# DE-060418.net
KiCad netlist of a schematic drawn in Altium Designer
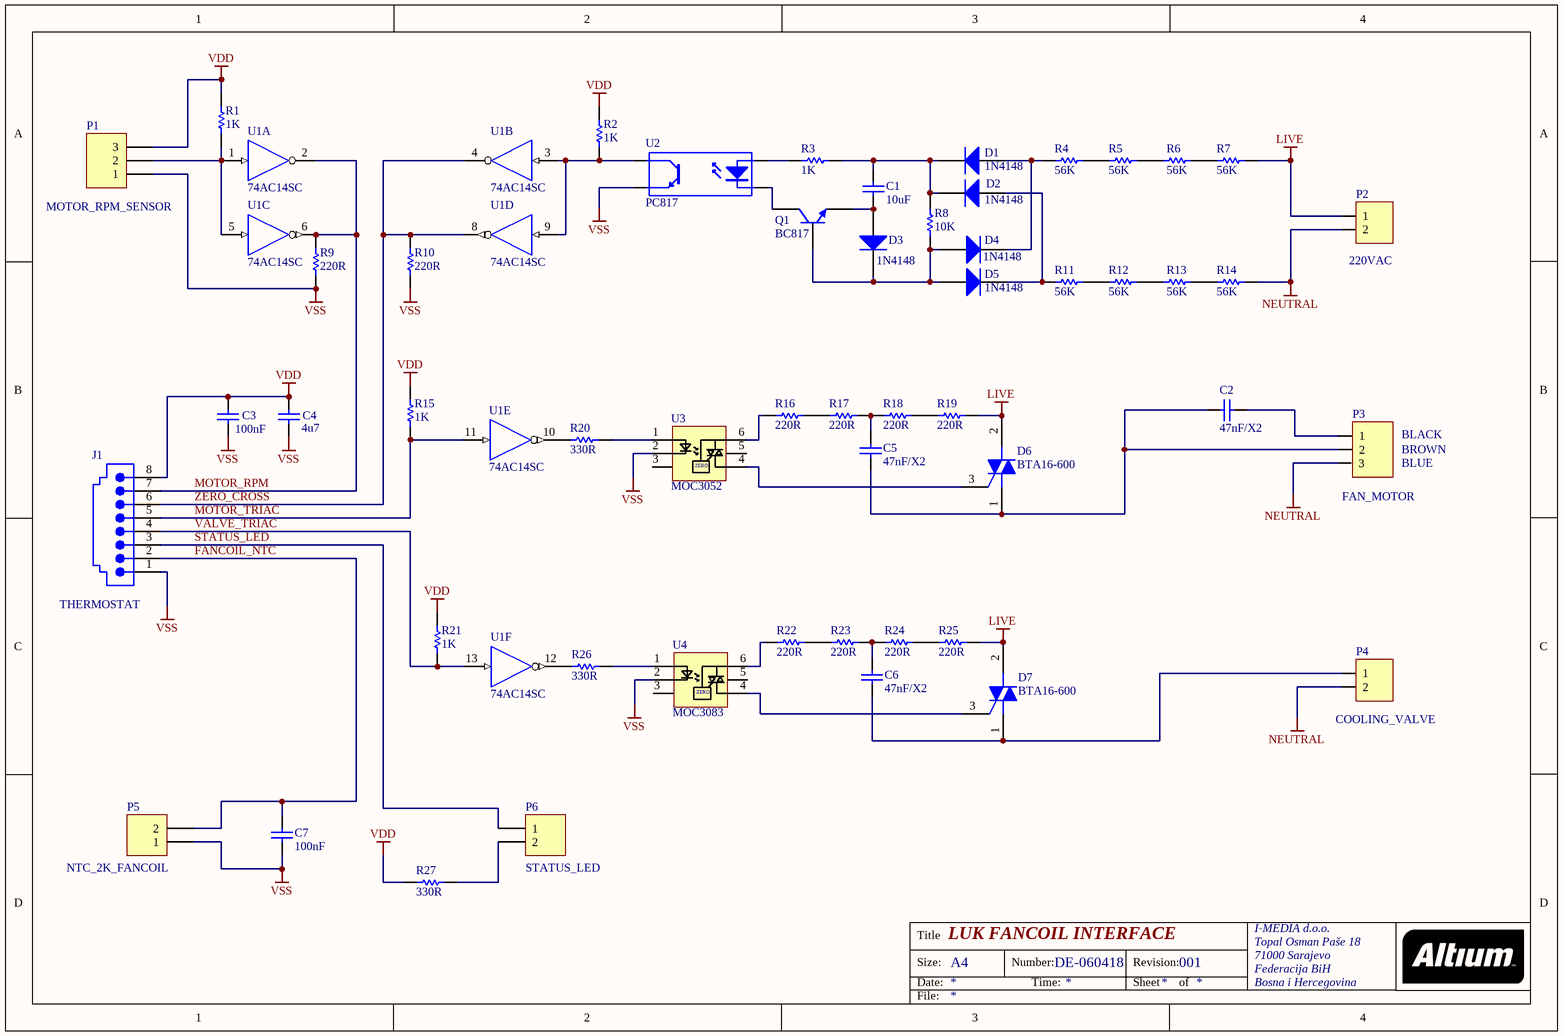
[diagram p0: DE-060418.SchDoc]

(export (version "E")
  (design (tool "Eeschema 10.0.6"))
  (components
    (comp (ref "C1")
      (value "10uF")
      (footprint "0805")
      (description "Ceramic Chip Capacitor - Standard")
      (fields (field (name "Comment") "4u7") (field (name "PUBLISHER") "Altium Limited"))
      (libsource (lib "DE-060418") (part "C0805"))
    )
    (comp (ref "C2")
      (value "47nF/X2")
      (footprint "VP52-2.5")
      (description "Dipped Radial Multilayer Ceramic Capacitor COG (NPO): 10nF")
      (fields (field (name "PUBLISHER") "Altium Limited"))
      (libsource (lib "Vishay Vitramon Ceramic Dipped Capacitor") (part "VP52BA103"))
    )
    (comp (ref "C3")
      (value "100nF")
      (footprint "0603")
      (description "Ceramic Chip Capacitor - Standard")
      (fields (field (name "PUBLISHER") "Altium Limited"))
      (libsource (lib "DE-060418") (part "C0603"))
    )
    (comp (ref "C4")
      (value "4u7")
      (footprint "0805")
      (description "Ceramic Chip Capacitor - Standard")
      (fields (field (name "PUBLISHER") "Altium Limited"))
      (libsource (lib "DE-060418") (part "C0805"))
    )
    (comp (ref "C5")
      (value "47nF/X2")
      (footprint "VP52-2.5")
      (description "Dipped Radial Multilayer Ceramic Capacitor COG (NPO): 10nF")
      (fields (field (name "PUBLISHER") "Altium Limited"))
      (libsource (lib "Vishay Vitramon Ceramic Dipped Capacitor") (part "VP52BA103"))
    )
    (comp (ref "C6")
      (value "47nF/X2")
      (footprint "VP52-2.5")
      (description "Dipped Radial Multilayer Ceramic Capacitor COG (NPO): 10nF")
      (fields (field (name "PUBLISHER") "Altium Limited"))
      (libsource (lib "Vishay Vitramon Ceramic Dipped Capacitor") (part "VP52BA103"))
    )
    (comp (ref "C7")
      (value "100nF")
      (footprint "0603")
      (description "Ceramic Chip Capacitor - Standard")
      (fields (field (name "PUBLISHER") "Altium Limited"))
      (libsource (lib "DE-060418") (part "C0603"))
    )
    (comp (ref "D1")
      (value "1N4148")
      (footprint "SOD323")
      (description "General-purpose Diode")
      (fields (field (name "PUBLISHER") "Altium Limited"))
      (libsource (lib "DE-060418") (part "BAS321"))
    )
    (comp (ref "D2")
      (value "1N4148")
      (footprint "SOD323")
      (description "General-purpose Diode")
      (fields (field (name "PUBLISHER") "Altium Limited"))
      (libsource (lib "DE-060418") (part "BAS321"))
    )
    (comp (ref "D3")
      (value "1N4148")
      (footprint "SOD323")
      (description "General-purpose Diode")
      (fields (field (name "PUBLISHER") "Altium Limited"))
      (libsource (lib "DE-060418") (part "BAS321"))
    )
    (comp (ref "D4")
      (value "1N4148")
      (footprint "SOD323")
      (description "General-purpose Diode")
      (fields (field (name "PUBLISHER") "Altium Limited"))
      (libsource (lib "DE-060418") (part "BAS321"))
    )
    (comp (ref "D5")
      (value "1N4148")
      (footprint "SOD323")
      (description "General-purpose Diode")
      (fields (field (name "PUBLISHER") "Altium Limited"))
      (libsource (lib "DE-060418") (part "BAS321"))
    )
    (comp (ref "D6")
      (value "BTA16-600")
      (footprint "ONSC-TO-220-3-221A-07")
      (description "Triacs, Silicon Bidirectional Thyristor, 3-Pin TO-220, Pb-Free, Tube")
      (fields (field (name "MANUFACTURER") "On Semiconductor") (field (name "PARTNUMBER") "BTA08-600BW3G"))
      (libsource (lib "ON Semi Triacs") (part "BTA08-600BW3G"))
    )
    (comp (ref "D7")
      (value "BTA16-600")
      (footprint "ONSC-TO-220-3-221A-07")
      (description "Triacs, Silicon Bidirectional Thyristor, 3-Pin TO-220, Pb-Free, Tube")
      (fields (field (name "MANUFACTURER") "On Semiconductor") (field (name "PARTNUMBER") "BTA08-600BW3G"))
      (libsource (lib "ON Semi Triacs") (part "BTA08-600BW3G"))
    )
    (comp (ref "J1")
      (value "THERMOSTAT")
      (footprint "15-43-8501")
      (description "Right Angle, Standard Profile, RJ-45 Keyed, Unshielded PCB Jack")
      (fields (field (name "PUBLISHER") "Altium Limited"))
      (libsource (lib "Molex Modular Jack Right Angle") (part "15-43-8501"))
    )
    (comp (ref "P1")
      (value "MOTOR_RPM_SENSOR")
      (footprint "HDR1X3")
      (description "Header, 3-Pin")
      (fields (field (name "PUBLISHER") "Altium Limited"))
      (libsource (lib "DE-060418") (part "Header 3"))
    )
    (comp (ref "P2")
      (value "220VAC")
      (footprint "TERMINAL BLOK 2")
      (description "Terminal blok konektor 3,5 mm")
      (libsource (lib "DE-060418") (part "TERMINAL BLOK 2"))
    )
    (comp (ref "P3")
      (value "FAN_MOTOR")
      (footprint "TERMINAL BLOK 3")
      (description "3 pinski terminal blok konektor")
      (libsource (lib "DE-060418") (part "TERMINAL BLOK 3"))
    )
    (comp (ref "P4")
      (value "COOLING_VALVE")
      (footprint "TERMINAL BLOK 2")
      (description "Terminal blok konektor 3,5 mm")
      (libsource (lib "DE-060418") (part "TERMINAL BLOK 2"))
    )
    (comp (ref "P5")
      (value "NTC_2K_FANCOIL")
      (footprint "HDR1X2")
      (description "Header, 2-Pin")
      (fields (field (name "PUBLISHER") "Altium Limited"))
      (libsource (lib "Miscellaneous Connectors") (part "Header 2"))
    )
    (comp (ref "P6")
      (value "STATUS_LED")
      (footprint "HDR1X2")
      (description "Header, 2-Pin")
      (fields (field (name "PUBLISHER") "Altium Limited"))
      (libsource (lib "") (part "Header 2_1"))
    )
    (comp (ref "Q1")
      (value "BC817")
      (footprint "SOT23_N")
      (description "NPN General-purpose Transistor")
      (fields (field (name "PUBLISHER") "Altium Limited"))
      (libsource (lib "DE-060418") (part "BC817"))
    )
    (comp (ref "R1")
      (value "1K")
      (footprint "6-0805")
      (fields (field (name "PUBLISHER") "Altium Limited"))
      (libsource (lib "Panasonic Resistor") (part "ERJ6BQ"))
    )
    (comp (ref "R2")
      (value "1K")
      (footprint "6-0805")
      (fields (field (name "PUBLISHER") "Altium Limited"))
      (libsource (lib "Panasonic Resistor") (part "ERJ6BQ"))
    )
    (comp (ref "R3")
      (value "1K")
      (footprint "6-0805")
      (fields (field (name "PUBLISHER") "Altium Limited"))
      (libsource (lib "Panasonic Resistor") (part "ERJ6BQ"))
    )
    (comp (ref "R4")
      (value "56K")
      (footprint "6-0805")
      (fields (field (name "PUBLISHER") "Altium Limited"))
      (libsource (lib "Panasonic Resistor") (part "ERJ6BQ"))
    )
    (comp (ref "R5")
      (value "56K")
      (footprint "6-0805")
      (fields (field (name "PUBLISHER") "Altium Limited"))
      (libsource (lib "Panasonic Resistor") (part "ERJ6BQ"))
    )
    (comp (ref "R6")
      (value "56K")
      (footprint "6-0805")
      (fields (field (name "PUBLISHER") "Altium Limited"))
      (libsource (lib "Panasonic Resistor") (part "ERJ6BQ"))
    )
    (comp (ref "R7")
      (value "56K")
      (footprint "6-0805")
      (fields (field (name "PUBLISHER") "Altium Limited"))
      (libsource (lib "Panasonic Resistor") (part "ERJ6BQ"))
    )
    (comp (ref "R8")
      (value "10K")
      (footprint "6-0805")
      (fields (field (name "PUBLISHER") "Altium Limited"))
      (libsource (lib "Panasonic Resistor") (part "ERJ6BQ"))
    )
    (comp (ref "R9")
      (value "220R")
      (footprint "6-0805")
      (fields (field (name "PUBLISHER") "Altium Limited"))
      (libsource (lib "Panasonic Resistor") (part "ERJ6BQ"))
    )
    (comp (ref "R10")
      (value "220R")
      (footprint "6-0805")
      (fields (field (name "PUBLISHER") "Altium Limited"))
      (libsource (lib "Panasonic Resistor") (part "ERJ6BQ"))
    )
    (comp (ref "R11")
      (value "56K")
      (footprint "6-0805")
      (fields (field (name "PUBLISHER") "Altium Limited"))
      (libsource (lib "Panasonic Resistor") (part "ERJ6BQ"))
    )
    (comp (ref "R12")
      (value "56K")
      (footprint "6-0805")
      (fields (field (name "PUBLISHER") "Altium Limited"))
      (libsource (lib "Panasonic Resistor") (part "ERJ6BQ"))
    )
    (comp (ref "R13")
      (value "56K")
      (footprint "6-0805")
      (fields (field (name "PUBLISHER") "Altium Limited"))
      (libsource (lib "Panasonic Resistor") (part "ERJ6BQ"))
    )
    (comp (ref "R14")
      (value "56K")
      (footprint "6-0805")
      (fields (field (name "PUBLISHER") "Altium Limited"))
      (libsource (lib "Panasonic Resistor") (part "ERJ6BQ"))
    )
    (comp (ref "R15")
      (value "1K")
      (footprint "6-0805")
      (fields (field (name "PUBLISHER") "Altium Limited"))
      (libsource (lib "Panasonic Resistor") (part "ERJ6BQ"))
    )
    (comp (ref "R16")
      (value "220R")
      (footprint "6-0805")
      (fields (field (name "PUBLISHER") "Altium Limited"))
      (libsource (lib "Panasonic Resistor") (part "ERJ6BQ"))
    )
    (comp (ref "R17")
      (value "220R")
      (footprint "6-0805")
      (fields (field (name "PUBLISHER") "Altium Limited"))
      (libsource (lib "Panasonic Resistor") (part "ERJ6BQ"))
    )
    (comp (ref "R18")
      (value "220R")
      (footprint "6-0805")
      (fields (field (name "PUBLISHER") "Altium Limited"))
      (libsource (lib "Panasonic Resistor") (part "ERJ6BQ"))
    )
    (comp (ref "R19")
      (value "220R")
      (footprint "6-0805")
      (fields (field (name "PUBLISHER") "Altium Limited"))
      (libsource (lib "Panasonic Resistor") (part "ERJ6BQ"))
    )
    (comp (ref "R20")
      (value "330R")
      (footprint "6-0805")
      (fields (field (name "PUBLISHER") "Altium Limited"))
      (libsource (lib "Panasonic Resistor") (part "ERJ6BQ"))
    )
    (comp (ref "R21")
      (value "1K")
      (footprint "6-0805")
      (fields (field (name "PUBLISHER") "Altium Limited"))
      (libsource (lib "Panasonic Resistor") (part "ERJ6BQ"))
    )
    (comp (ref "R22")
      (value "220R")
      (footprint "6-0805")
      (fields (field (name "PUBLISHER") "Altium Limited"))
      (libsource (lib "Panasonic Resistor") (part "ERJ6BQ"))
    )
    (comp (ref "R23")
      (value "220R")
      (footprint "6-0805")
      (fields (field (name "PUBLISHER") "Altium Limited"))
      (libsource (lib "Panasonic Resistor") (part "ERJ6BQ"))
    )
    (comp (ref "R24")
      (value "220R")
      (footprint "6-0805")
      (fields (field (name "PUBLISHER") "Altium Limited"))
      (libsource (lib "Panasonic Resistor") (part "ERJ6BQ"))
    )
    (comp (ref "R25")
      (value "220R")
      (footprint "6-0805")
      (fields (field (name "PUBLISHER") "Altium Limited"))
      (libsource (lib "Panasonic Resistor") (part "ERJ6BQ"))
    )
    (comp (ref "R26")
      (value "330R")
      (footprint "6-0805")
      (fields (field (name "PUBLISHER") "Altium Limited"))
      (libsource (lib "Panasonic Resistor") (part "ERJ6BQ"))
    )
    (comp (ref "R27")
      (value "330R")
      (footprint "6-0805")
      (fields (field (name "PUBLISHER") "Altium Limited"))
      (libsource (lib "Panasonic Resistor") (part "ERJ6BQ"))
    )
    (comp (ref "U1")
      (value "74AC14SC")
      (footprint "M14A_N")
      (description "Hex Schmitt-Trigger Inverter, 14-Pin SOIC, Commercial Grade")
      (fields (field (name "PUBLISHER") "Altium Limited"))
      (libsource (lib "FSC Logic Gate") (part "74AC14SC"))
    )
    (comp (ref "U2")
      (value "PC817")
      (footprint "DIP-4")
      (description "4-Pin Phototransistor Optocoupler")
      (fields (field (name "PUBLISHER") "Altium Limited"))
      (libsource (lib "DE-060418") (part "Optoisolator1"))
    )
    (comp (ref "U3")
      (value "MOC3052")
      (footprint "DIP6")
      (description "Zero-Cross Optoisolator Triac Driver")
      (libsource (lib "DE-060418") (part "MOC3081"))
    )
    (comp (ref "U4")
      (value "MOC3083")
      (footprint "DIP6")
      (description "Zero-Cross Optoisolator Triac Driver")
      (libsource (lib "DE-060418") (part "MOC3081"))
    )
  )
  (nets
    (net (code "1") (name "/FANCOIL_NTC") (class "Default")
      (node (ref "C7") (pin "2") (pinfunction "2_2") (pintype "passive"))
      (node (ref "J1") (pin "2") (pinfunction "2_2") (pintype "passive"))
      (node (ref "P5") (pin "2") (pinfunction "2_2") (pintype "passive"))
    )
    (net (code "2") (name "/MOTOR_RPM") (class "Default")
      (node (ref "J1") (pin "7") (pinfunction "7_7") (pintype "passive"))
      (node (ref "R9") (pin "1") (pinfunction "1_1") (pintype "passive"))
      (node (ref "U1") (pin "2") (pinfunction "~{O}_2") (pintype "output"))
      (node (ref "U1") (pin "6") (pinfunction "~{O}_6") (pintype "output"))
    )
    (net (code "3") (name "/MOTOR_TRIAC") (class "Default")
      (node (ref "J1") (pin "5") (pinfunction "5_5") (pintype "passive"))
      (node (ref "R15") (pin "2") (pinfunction "2_2") (pintype "passive"))
      (node (ref "U1") (pin "11") (pinfunction "I_11") (pintype "input"))
    )
    (net (code "4") (name "/STATUS_LED") (class "Default")
      (node (ref "J1") (pin "3") (pinfunction "3_3") (pintype "passive"))
      (node (ref "P6") (pin "1") (pinfunction "1_1") (pintype "passive"))
    )
    (net (code "5") (name "/VALVE_TRIAC") (class "Default")
      (node (ref "J1") (pin "4") (pinfunction "4_4") (pintype "passive"))
      (node (ref "R21") (pin "2") (pinfunction "2_2") (pintype "passive"))
      (node (ref "U1") (pin "13") (pinfunction "I_13") (pintype "input"))
    )
    (net (code "6") (name "/ZERO_CROSS") (class "Default")
      (node (ref "J1") (pin "6") (pinfunction "6_6") (pintype "passive"))
      (node (ref "R10") (pin "1") (pinfunction "1_1") (pintype "passive"))
      (node (ref "U1") (pin "4") (pinfunction "~{O}_4") (pintype "output"))
      (node (ref "U1") (pin "8") (pinfunction "~{O}_8") (pintype "output"))
    )
    (net (code "7") (name "LIVE") (class "Default")
      (node (ref "D6") (pin "2") (pinfunction "MT2_2") (pintype "passive"))
      (node (ref "D7") (pin "2") (pinfunction "MT2_2") (pintype "passive"))
      (node (ref "P2") (pin "1") (pinfunction "1_1") (pintype "passive"))
      (node (ref "R19") (pin "2") (pinfunction "2_2") (pintype "passive"))
      (node (ref "R25") (pin "2") (pinfunction "2_2") (pintype "passive"))
      (node (ref "R7") (pin "2") (pinfunction "2_2") (pintype "passive"))
    )
    (net (code "8") (name "NEUTRAL") (class "Default")
      (node (ref "P2") (pin "2") (pinfunction "2_2") (pintype "passive"))
      (node (ref "P3") (pin "3") (pinfunction "3_3") (pintype "passive"))
      (node (ref "P4") (pin "2") (pinfunction "2_2") (pintype "passive"))
      (node (ref "R14") (pin "2") (pinfunction "2_2") (pintype "passive"))
    )
    (net (code "9") (name "Net-(C2-Pad2)") (class "Default")
      (node (ref "C2") (pin "2") (pinfunction "2_2") (pintype "passive"))
      (node (ref "P3") (pin "1") (pinfunction "1_1") (pintype "passive"))
    )
    (net (code "10") (name "Net-(C5-Pad2)") (class "Default")
      (node (ref "C5") (pin "2") (pinfunction "2_2") (pintype "passive"))
      (node (ref "R17") (pin "2") (pinfunction "2_2") (pintype "passive"))
      (node (ref "R18") (pin "1") (pinfunction "1_1") (pintype "passive"))
    )
    (net (code "11") (name "Net-(C6-Pad2)") (class "Default")
      (node (ref "C6") (pin "2") (pinfunction "2_2") (pintype "passive"))
      (node (ref "R23") (pin "2") (pinfunction "2_2") (pintype "passive"))
      (node (ref "R24") (pin "1") (pinfunction "1_1") (pintype "passive"))
    )
    (net (code "12") (name "Net-(D1-A)") (class "Default")
      (node (ref "D1") (pin "2") (pinfunction "A_2") (pintype "passive"))
      (node (ref "D4") (pin "1") (pinfunction "K_1") (pintype "passive"))
      (node (ref "R4") (pin "1") (pinfunction "1_1") (pintype "passive"))
    )
    (net (code "13") (name "Net-(D1-K)") (class "Default")
      (node (ref "C1") (pin "2") (pinfunction "2_2") (pintype "passive"))
      (node (ref "D1") (pin "1") (pinfunction "K_1") (pintype "passive"))
      (node (ref "D2") (pin "1") (pinfunction "K_1") (pintype "passive"))
      (node (ref "R3") (pin "2") (pinfunction "2_2") (pintype "passive"))
      (node (ref "R8") (pin "2") (pinfunction "2_2") (pintype "passive"))
    )
    (net (code "14") (name "Net-(D2-A)") (class "Default")
      (node (ref "D2") (pin "2") (pinfunction "A_2") (pintype "passive"))
      (node (ref "D5") (pin "1") (pinfunction "K_1") (pintype "passive"))
      (node (ref "R11") (pin "1") (pinfunction "1_1") (pintype "passive"))
    )
    (net (code "15") (name "Net-(D3-A)") (class "Default")
      (node (ref "C1") (pin "1") (pinfunction "1_1") (pintype "passive"))
      (node (ref "D3") (pin "2") (pinfunction "A_2") (pintype "passive"))
      (node (ref "Q1") (pin "2") (pinfunction "E_2") (pintype "passive"))
    )
    (net (code "16") (name "Net-(D3-K)") (class "Default")
      (node (ref "D3") (pin "1") (pinfunction "K_1") (pintype "passive"))
      (node (ref "D4") (pin "2") (pinfunction "A_2") (pintype "passive"))
      (node (ref "D5") (pin "2") (pinfunction "A_2") (pintype "passive"))
      (node (ref "Q1") (pin "1") (pinfunction "B_1") (pintype "passive"))
      (node (ref "R8") (pin "1") (pinfunction "1_1") (pintype "passive"))
    )
    (net (code "17") (name "Net-(D6-G)") (class "Default")
      (node (ref "D6") (pin "3") (pinfunction "G_3") (pintype "passive"))
      (node (ref "U3") (pin "4") (pinfunction "4_4") (pintype "passive"))
    )
    (net (code "18") (name "Net-(D6-MT1)") (class "Default")
      (node (ref "C2") (pin "1") (pinfunction "1_1") (pintype "passive"))
      (node (ref "C5") (pin "1") (pinfunction "1_1") (pintype "passive"))
      (node (ref "D6") (pin "1") (pinfunction "MT1_1") (pintype "passive"))
      (node (ref "P3") (pin "2") (pinfunction "2_2") (pintype "passive"))
    )
    (net (code "19") (name "Net-(D7-G)") (class "Default")
      (node (ref "D7") (pin "3") (pinfunction "G_3") (pintype "passive"))
      (node (ref "U4") (pin "4") (pinfunction "4_4") (pintype "passive"))
    )
    (net (code "20") (name "Net-(D7-MT1)") (class "Default")
      (node (ref "C6") (pin "1") (pinfunction "1_1") (pintype "passive"))
      (node (ref "D7") (pin "1") (pinfunction "MT1_1") (pintype "passive"))
      (node (ref "P4") (pin "1") (pinfunction "1_1") (pintype "passive"))
    )
    (net (code "21") (name "Net-(P6-Pad2)") (class "Default")
      (node (ref "P6") (pin "2") (pinfunction "2_2") (pintype "passive"))
      (node (ref "R27") (pin "2") (pinfunction "2_2") (pintype "passive"))
    )
    (net (code "22") (name "Net-(Q1-C)") (class "Default")
      (node (ref "Q1") (pin "3") (pinfunction "C_3") (pintype "passive"))
      (node (ref "U2") (pin "2") (pinfunction "K_2") (pintype "passive"))
    )
    (net (code "23") (name "Net-(R4-Pad2)") (class "Default")
      (node (ref "R4") (pin "2") (pinfunction "2_2") (pintype "passive"))
      (node (ref "R5") (pin "1") (pinfunction "1_1") (pintype "passive"))
    )
    (net (code "24") (name "Net-(R5-Pad2)") (class "Default")
      (node (ref "R5") (pin "2") (pinfunction "2_2") (pintype "passive"))
      (node (ref "R6") (pin "1") (pinfunction "1_1") (pintype "passive"))
    )
    (net (code "25") (name "Net-(R6-Pad2)") (class "Default")
      (node (ref "R6") (pin "2") (pinfunction "2_2") (pintype "passive"))
      (node (ref "R7") (pin "1") (pinfunction "1_1") (pintype "passive"))
    )
    (net (code "26") (name "Net-(R11-Pad2)") (class "Default")
      (node (ref "R11") (pin "2") (pinfunction "2_2") (pintype "passive"))
      (node (ref "R12") (pin "1") (pinfunction "1_1") (pintype "passive"))
    )
    (net (code "27") (name "Net-(R12-Pad2)") (class "Default")
      (node (ref "R12") (pin "2") (pinfunction "2_2") (pintype "passive"))
      (node (ref "R13") (pin "1") (pinfunction "1_1") (pintype "passive"))
    )
    (net (code "28") (name "Net-(R13-Pad2)") (class "Default")
      (node (ref "R13") (pin "2") (pinfunction "2_2") (pintype "passive"))
      (node (ref "R14") (pin "1") (pinfunction "1_1") (pintype "passive"))
    )
    (net (code "29") (name "Net-(R16-Pad1)") (class "Default")
      (node (ref "R16") (pin "1") (pinfunction "1_1") (pintype "passive"))
      (node (ref "U3") (pin "6") (pinfunction "6_6") (pintype "passive"))
    )
    (net (code "30") (name "Net-(R16-Pad2)") (class "Default")
      (node (ref "R16") (pin "2") (pinfunction "2_2") (pintype "passive"))
      (node (ref "R17") (pin "1") (pinfunction "1_1") (pintype "passive"))
    )
    (net (code "31") (name "Net-(R18-Pad2)") (class "Default")
      (node (ref "R18") (pin "2") (pinfunction "2_2") (pintype "passive"))
      (node (ref "R19") (pin "1") (pinfunction "1_1") (pintype "passive"))
    )
    (net (code "32") (name "Net-(R20-Pad1)") (class "Default")
      (node (ref "R20") (pin "1") (pinfunction "1_1") (pintype "passive"))
      (node (ref "U3") (pin "1") (pinfunction "1_1") (pintype "passive"))
    )
    (net (code "33") (name "Net-(R22-Pad1)") (class "Default")
      (node (ref "R22") (pin "1") (pinfunction "1_1") (pintype "passive"))
      (node (ref "U4") (pin "6") (pinfunction "6_6") (pintype "passive"))
    )
    (net (code "34") (name "Net-(R22-Pad2)") (class "Default")
      (node (ref "R22") (pin "2") (pinfunction "2_2") (pintype "passive"))
      (node (ref "R23") (pin "1") (pinfunction "1_1") (pintype "passive"))
    )
    (net (code "35") (name "Net-(R24-Pad2)") (class "Default")
      (node (ref "R24") (pin "2") (pinfunction "2_2") (pintype "passive"))
      (node (ref "R25") (pin "1") (pinfunction "1_1") (pintype "passive"))
    )
    (net (code "36") (name "Net-(R26-Pad1)") (class "Default")
      (node (ref "R26") (pin "1") (pinfunction "1_1") (pintype "passive"))
      (node (ref "U4") (pin "1") (pinfunction "1_1") (pintype "passive"))
    )
    (net (code "37") (name "Net-(U1A-I)") (class "Default")
      (node (ref "P1") (pin "2") (pinfunction "2_2") (pintype "passive"))
      (node (ref "R1") (pin "2") (pinfunction "2_2") (pintype "passive"))
      (node (ref "U1") (pin "1") (pinfunction "I_1") (pintype "input"))
      (node (ref "U1") (pin "5") (pinfunction "I_5") (pintype "input"))
    )
    (net (code "38") (name "Net-(U1B-I)") (class "Default")
      (node (ref "R2") (pin "2") (pinfunction "2_2") (pintype "passive"))
      (node (ref "U1") (pin "3") (pinfunction "I_3") (pintype "input"))
      (node (ref "U1") (pin "9") (pinfunction "I_9") (pintype "input"))
      (node (ref "U2") (pin "4") (pinfunction "C_4") (pintype "passive"))
    )
    (net (code "39") (name "Net-(U1E-~{O})") (class "Default")
      (node (ref "R20") (pin "2") (pinfunction "2_2") (pintype "passive"))
      (node (ref "U1") (pin "10") (pinfunction "~{O}_10") (pintype "output"))
    )
    (net (code "40") (name "Net-(U1F-~{O})") (class "Default")
      (node (ref "R26") (pin "2") (pinfunction "2_2") (pintype "passive"))
      (node (ref "U1") (pin "12") (pinfunction "~{O}_12") (pintype "output"))
    )
    (net (code "41") (name "Net-(U2-A)") (class "Default")
      (node (ref "R3") (pin "1") (pinfunction "1_1") (pintype "passive"))
      (node (ref "U2") (pin "1") (pinfunction "A_1") (pintype "passive"))
    )
    (net (code "42") (name "VDD") (class "Default")
      (node (ref "C3") (pin "2") (pinfunction "2_2") (pintype "passive"))
      (node (ref "C4") (pin "2") (pinfunction "2_2") (pintype "passive"))
      (node (ref "J1") (pin "8") (pinfunction "8_8") (pintype "passive"))
      (node (ref "P1") (pin "3") (pinfunction "3_3") (pintype "passive"))
      (node (ref "R1") (pin "1") (pinfunction "1_1") (pintype "passive"))
      (node (ref "R15") (pin "1") (pinfunction "1_1") (pintype "passive"))
      (node (ref "R2") (pin "1") (pinfunction "1_1") (pintype "passive"))
      (node (ref "R21") (pin "1") (pinfunction "1_1") (pintype "passive"))
      (node (ref "R27") (pin "1") (pinfunction "1_1") (pintype "passive"))
      (node (ref "U1") (pin "14") (pinfunction "VDD_14") (pintype "power_in"))
    )
    (net (code "43") (name "VSS") (class "Default")
      (node (ref "C3") (pin "1") (pinfunction "1_1") (pintype "passive"))
      (node (ref "C4") (pin "1") (pinfunction "1_1") (pintype "passive"))
      (node (ref "C7") (pin "1") (pinfunction "1_1") (pintype "passive"))
      (node (ref "J1") (pin "1") (pinfunction "1_1") (pintype "passive"))
      (node (ref "P1") (pin "1") (pinfunction "1_1") (pintype "passive"))
      (node (ref "P5") (pin "1") (pinfunction "1_1") (pintype "passive"))
      (node (ref "R10") (pin "2") (pinfunction "2_2") (pintype "passive"))
      (node (ref "R9") (pin "2") (pinfunction "2_2") (pintype "passive"))
      (node (ref "U1") (pin "7") (pinfunction "VSS_7") (pintype "power_in"))
      (node (ref "U2") (pin "3") (pinfunction "E_3") (pintype "passive"))
      (node (ref "U3") (pin "2") (pinfunction "2_2") (pintype "passive"))
      (node (ref "U4") (pin "2") (pinfunction "2_2") (pintype "passive"))
    )
    (net (code "44") (name "unconnected-(U3-Pad3)") (class "Default")
      (node (ref "U3") (pin "3") (pinfunction "3_3") (pintype "passive"))
    )
    (net (code "45") (name "unconnected-(U3-Pad5)") (class "Default")
      (node (ref "U3") (pin "5") (pinfunction "5_5") (pintype "passive"))
    )
    (net (code "46") (name "unconnected-(U4-Pad3)") (class "Default")
      (node (ref "U4") (pin "3") (pinfunction "3_3") (pintype "passive"))
    )
    (net (code "47") (name "unconnected-(U4-Pad5)") (class "Default")
      (node (ref "U4") (pin "5") (pinfunction "5_5") (pintype "passive"))
    )
  )
)
